# esquematicoEagle.net
KiCad netlist of a schematic drawn in EAGLE
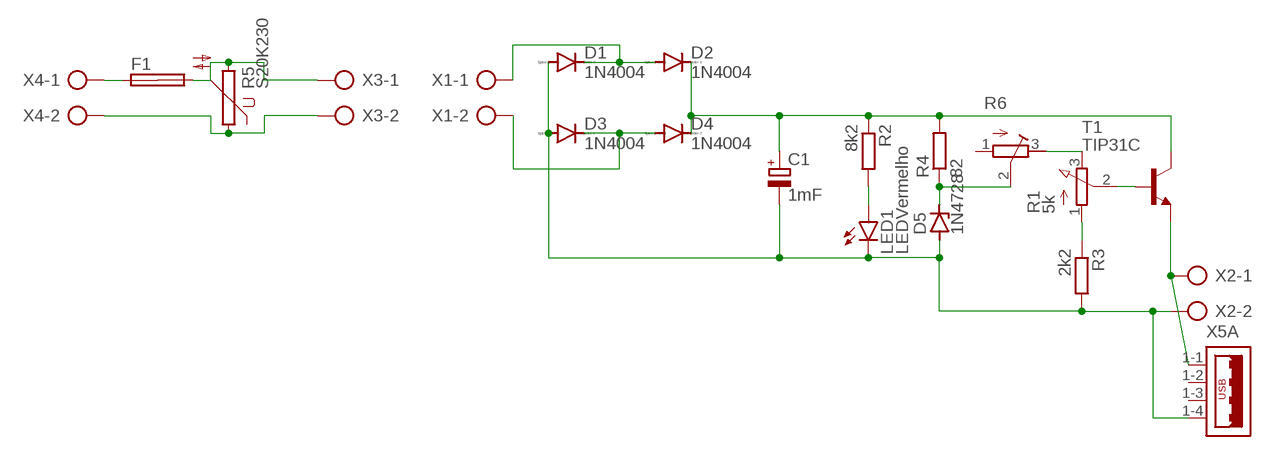
[diagram p0: schematic, sheet 1]

(export (version "E")
  (design (tool "Eeschema 10.0.6"))
  (components
    (comp (ref "C1")
      (value "1mF")
      (footprint "eagle-import:E5-10,5")
      (libsource (lib "eagle-import") (part "CPOL-EUE5-10.5"))
    )
    (comp (ref "D1")
      (value "1N4004")
      (footprint "eagle-import:DO41-10")
      (libsource (lib "eagle-import") (part "1N4004"))
    )
    (comp (ref "D2")
      (value "1N4004")
      (footprint "eagle-import:DO41-10")
      (libsource (lib "eagle-import") (part "1N4004"))
    )
    (comp (ref "D3")
      (value "1N4004")
      (footprint "eagle-import:DO41-10")
      (libsource (lib "eagle-import") (part "1N4004"))
    )
    (comp (ref "D4")
      (value "1N4004")
      (footprint "eagle-import:DO41-10")
      (libsource (lib "eagle-import") (part "1N4004"))
    )
    (comp (ref "D5")
      (value "1N4728")
      (footprint "eagle-import:DO41Z10")
      (libsource (lib "eagle-import") (part "1N4728"))
    )
    (comp (ref "F1")
      (value "SHK20L")
      (footprint "eagle-import:SHK20L")
      (libsource (lib "eagle-import") (part "SHK20L"))
    )
    (comp (ref "LED1")
      (value "LEDVermelho")
      (footprint "eagle-import:LED5MM")
      (libsource (lib "eagle-import") (part "LED5MM"))
    )
    (comp (ref "R1")
      (value "5k")
      (footprint "eagle-import:3RP_1610N")
      (libsource (lib "eagle-import") (part "3RP/1610N"))
    )
    (comp (ref "R2")
      (value "8k2")
      (footprint "eagle-import:0204_7")
      (libsource (lib "eagle-import") (part "R-EU_0204/7"))
    )
    (comp (ref "R3")
      (value "2k2")
      (footprint "eagle-import:0204_7")
      (libsource (lib "eagle-import") (part "R-EU_0204/7"))
    )
    (comp (ref "R4")
      (value "82")
      (footprint "eagle-import:0204_7")
      (libsource (lib "eagle-import") (part "R-EU_0204/7"))
    )
    (comp (ref "R5")
      (value "S20K230")
      (footprint "eagle-import:S20K230")
      (libsource (lib "eagle-import") (part "S20K230"))
    )
    (comp (ref "R6")
      (value "R-TRIMM3296W")
      (footprint "eagle-import:RTRIM3296W")
      (libsource (lib "eagle-import") (part "R-TRIMM3296W"))
    )
    (comp (ref "T1")
      (value "TIP31C")
      (footprint "eagle-import:TO220")
      (libsource (lib "eagle-import") (part "TIP31C"))
    )
    (comp (ref "X1")
      (value "AK500/2-H")
      (footprint "eagle-import:AK500_2-H")
      (libsource (lib "eagle-import") (part "AK500/2-H"))
    )
    (comp (ref "X2")
      (value "AK500/2-H")
      (footprint "eagle-import:AK500_2-H")
      (libsource (lib "eagle-import") (part "AK500/2-H"))
    )
    (comp (ref "X3")
      (value "AK500/2-H")
      (footprint "eagle-import:AK500_2-H")
      (libsource (lib "eagle-import") (part "AK500/2-H"))
    )
    (comp (ref "X4")
      (value "AK500/2-H")
      (footprint "eagle-import:AK500_2-H")
      (libsource (lib "eagle-import") (part "AK500/2-H"))
    )
    (comp (ref "X5")
      (value "USB_4-32003-40XA")
      (footprint "eagle-import:32003-40XA")
      (libsource (lib "eagle-import") (part "USB_4-32003-40XA"))
    )
  )
  (nets
    (net (code "1") (name "Net-(LED1-C)") (class "Default")
      (node (ref "C1") (pin "-") (pinfunction "-_-") (pintype "passive"))
      (node (ref "D1") (pin "A") (pinfunction "A_A") (pintype "passive"))
      (node (ref "D3") (pin "A") (pinfunction "A_A") (pintype "passive"))
      (node (ref "D5") (pin "A") (pinfunction "A_A") (pintype "passive"))
      (node (ref "LED1") (pin "K") (pinfunction "C_K") (pintype "passive"))
      (node (ref "R3") (pin "2") (pinfunction "2_2") (pintype "passive"))
      (node (ref "X2") (pin "2") (pinfunction "KL_2") (pintype "passive"))
      (node (ref "X5") (pin "1-4") (pinfunction "4_1-4") (pintype "passive"))
    )
    (net (code "2") (name "Net-(LED1-PadA)") (class "Default")
      (node (ref "LED1") (pin "A") (pinfunction "A_A") (pintype "passive"))
      (node (ref "R2") (pin "2") (pinfunction "2_2") (pintype "passive"))
    )
    (net (code "3") (name "Net-(R1-A)") (class "Default")
      (node (ref "R1") (pin "1") (pinfunction "A_1") (pintype "passive"))
      (node (ref "R3") (pin "1") (pinfunction "1_1") (pintype "passive"))
    )
    (net (code "4") (name "Net-(R1-E)") (class "Default")
      (node (ref "R1") (pin "3") (pinfunction "E_3") (pintype "passive"))
      (node (ref "R6") (pin "3") (pinfunction "E_3") (pintype "passive"))
    )
    (net (code "5") (name "Net-(R1-S)") (class "Default")
      (node (ref "R1") (pin "2") (pinfunction "S_2") (pintype "passive"))
      (node (ref "T1") (pin "1") (pinfunction "B_1") (pintype "passive"))
    )
    (net (code "6") (name "Net-(R6-S)") (class "Default")
      (node (ref "D5") (pin "C") (pinfunction "C_C") (pintype "passive"))
      (node (ref "R4") (pin "1") (pinfunction "1_1") (pintype "passive"))
      (node (ref "R6") (pin "2") (pinfunction "S_2") (pintype "passive"))
    )
    (net (code "7") (name "Net-(T1-C)") (class "Default")
      (node (ref "C1") (pin "+") (pinfunction "+_+") (pintype "passive"))
      (node (ref "D2") (pin "C") (pinfunction "C_C") (pintype "passive"))
      (node (ref "D4") (pin "C") (pinfunction "C_C") (pintype "passive"))
      (node (ref "R2") (pin "1") (pinfunction "1_1") (pintype "passive"))
      (node (ref "R4") (pin "2") (pinfunction "2_2") (pintype "passive"))
      (node (ref "T1") (pin "2") (pinfunction "C_2") (pintype "passive"))
    )
    (net (code "8") (name "Net-(T1-E)") (class "Default")
      (node (ref "T1") (pin "3") (pinfunction "E_3") (pintype "passive"))
      (node (ref "X2") (pin "1") (pinfunction "KL_1") (pintype "passive"))
      (node (ref "X5") (pin "1-1") (pinfunction "1_1-1") (pintype "passive"))
    )
    (net (code "9") (name "Net-(X1A-KL)") (class "Default")
      (node (ref "D1") (pin "C") (pinfunction "C_C") (pintype "passive"))
      (node (ref "D2") (pin "A") (pinfunction "A_A") (pintype "passive"))
      (node (ref "X1") (pin "1") (pinfunction "KL_1") (pintype "passive"))
    )
    (net (code "10") (name "Net-(X1B-KL)") (class "Default")
      (node (ref "D3") (pin "C") (pinfunction "C_C") (pintype "passive"))
      (node (ref "D4") (pin "A") (pinfunction "A_A") (pintype "passive"))
      (node (ref "X1") (pin "2") (pinfunction "KL_2") (pintype "passive"))
    )
    (net (code "11") (name "Net-(X3A-KL)") (class "Default")
      (node (ref "F1") (pin "2A") (pinfunction "2A_2A") (pintype "passive"))
      (node (ref "R5") (pin "2") (pinfunction "2_2") (pintype "passive"))
      (node (ref "X3") (pin "1") (pinfunction "KL_1") (pintype "passive"))
    )
    (net (code "12") (name "Net-(X3B-KL)") (class "Default")
      (node (ref "R5") (pin "1") (pinfunction "1_1") (pintype "passive"))
      (node (ref "X3") (pin "2") (pinfunction "KL_2") (pintype "passive"))
      (node (ref "X4") (pin "2") (pinfunction "KL_2") (pintype "passive"))
    )
    (net (code "13") (name "Net-(X4A-KL)") (class "Default")
      (node (ref "F1") (pin "1A") (pinfunction "1A_1A") (pintype "passive"))
      (node (ref "X4") (pin "1") (pinfunction "KL_1") (pintype "passive"))
    )
    (net (code "14") (name "unconnected-(F1-Pad1B)") (class "Default")
      (node (ref "F1") (pin "1B") (pinfunction "1B_1B") (pintype "passive"))
    )
    (net (code "15") (name "unconnected-(F1-Pad2B)") (class "Default")
      (node (ref "F1") (pin "2B") (pinfunction "2B_2B") (pintype "passive"))
    )
    (net (code "16") (name "unconnected-(R6-A-Pad1)") (class "Default")
      (node (ref "R6") (pin "1") (pinfunction "A_1") (pintype "passive"))
    )
    (net (code "17") (name "unconnected-(X5A-2-Pad1-2)") (class "Default")
      (node (ref "X5") (pin "1-2") (pinfunction "2_1-2") (pintype "passive"))
    )
    (net (code "18") (name "unconnected-(X5A-3-Pad1-3)") (class "Default")
      (node (ref "X5") (pin "1-3") (pinfunction "3_1-3") (pintype "passive"))
    )
  )
)
